# FRDM-Robot-Rev1_8.net
KiCad netlist of a schematic drawn in EAGLE
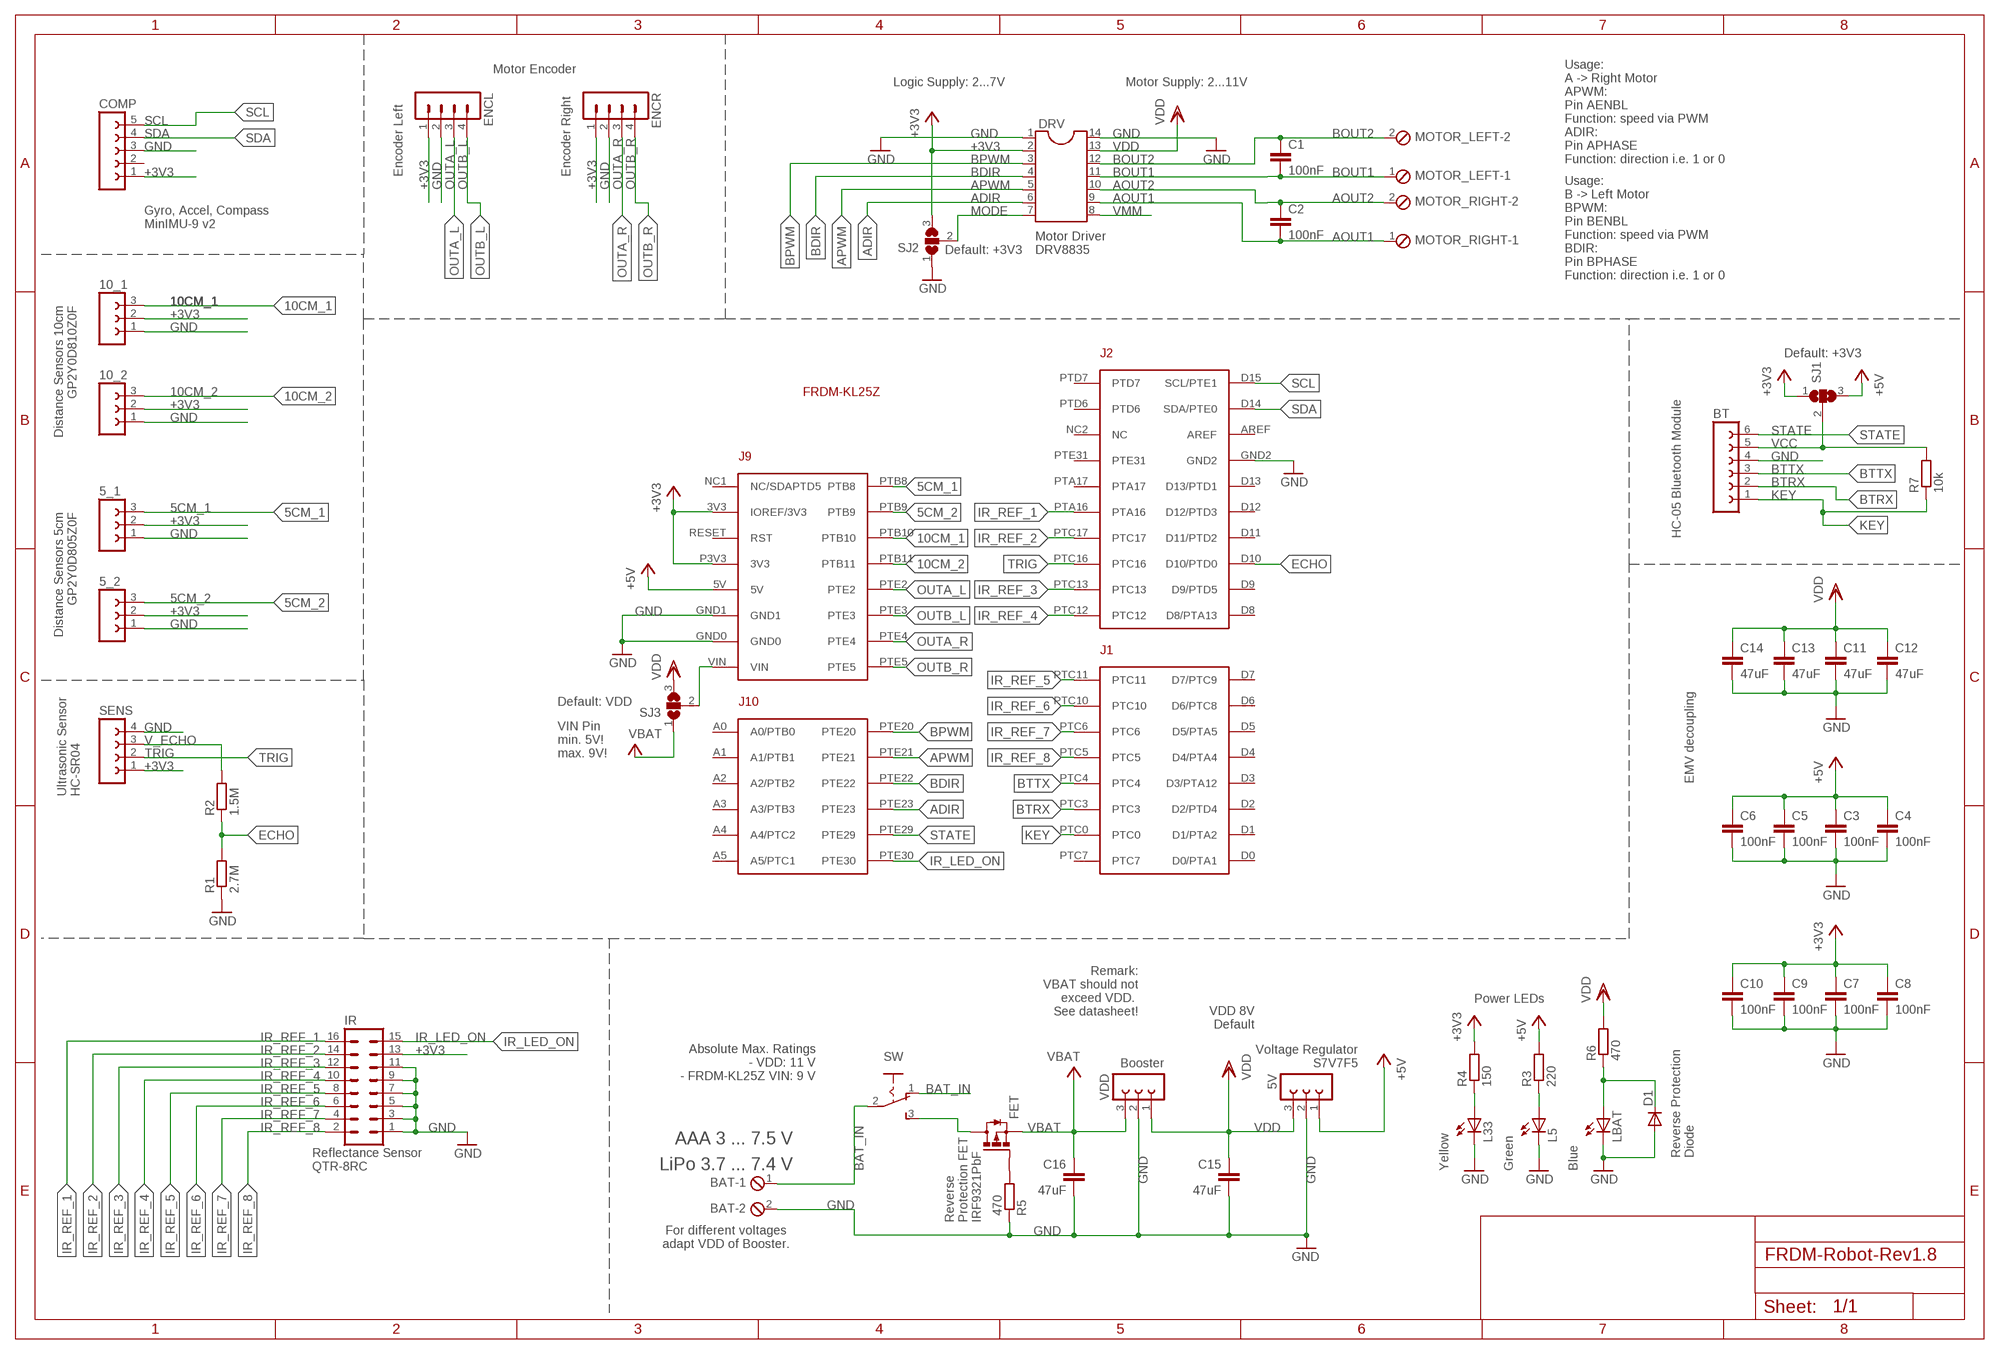
[diagram p0: schematic, sheet 1]

(export (version "E")
  (design (tool "Eeschema 10.0.6"))
  (components
    (comp (ref "5V")
      (value "FE03-1")
      (footprint "eagle-import:FE03-1")
      (libsource (lib "eagle-import") (part "FE03-1"))
    )
    (comp (ref "5_1")
      (value "FE03-1")
      (footprint "eagle-import:FE03-1")
      (libsource (lib "eagle-import") (part "FE03-1"))
    )
    (comp (ref "5_2")
      (value "FE03-1")
      (footprint "eagle-import:FE03-1")
      (libsource (lib "eagle-import") (part "FE03-1"))
    )
    (comp (ref "10_1")
      (value "FE03-1")
      (footprint "eagle-import:FE03-1")
      (libsource (lib "eagle-import") (part "FE03-1"))
    )
    (comp (ref "10_2")
      (value "FE03-1")
      (footprint "eagle-import:FE03-1")
      (libsource (lib "eagle-import") (part "FE03-1"))
    )
    (comp (ref "BAT")
      (value "MPT2")
      (footprint "eagle-import:2POL254")
      (libsource (lib "eagle-import") (part "MPT2"))
    )
    (comp (ref "BT")
      (value "FE06-1")
      (footprint "eagle-import:FE06")
      (libsource (lib "eagle-import") (part "FE06-1"))
    )
    (comp (ref "C1")
      (value "100nF")
      (footprint "eagle-import:C0805")
      (libsource (lib "eagle-import") (part "C-EUC0805"))
    )
    (comp (ref "C2")
      (value "100nF")
      (footprint "eagle-import:C0805")
      (libsource (lib "eagle-import") (part "C-EUC0805"))
    )
    (comp (ref "C3")
      (value "100nF")
      (footprint "eagle-import:C0805")
      (libsource (lib "eagle-import") (part "C-EUC0805"))
    )
    (comp (ref "C4")
      (value "100nF")
      (footprint "eagle-import:C0805")
      (libsource (lib "eagle-import") (part "C-EUC0805"))
    )
    (comp (ref "C5")
      (value "100nF")
      (footprint "eagle-import:C0805")
      (libsource (lib "eagle-import") (part "C-EUC0805"))
    )
    (comp (ref "C6")
      (value "100nF")
      (footprint "eagle-import:C0805")
      (libsource (lib "eagle-import") (part "C-EUC0805"))
    )
    (comp (ref "C7")
      (value "100nF")
      (footprint "eagle-import:C0805")
      (libsource (lib "eagle-import") (part "C-EUC0805"))
    )
    (comp (ref "C8")
      (value "100nF")
      (footprint "eagle-import:C0805")
      (libsource (lib "eagle-import") (part "C-EUC0805"))
    )
    (comp (ref "C9")
      (value "100nF")
      (footprint "eagle-import:C0805")
      (libsource (lib "eagle-import") (part "C-EUC0805"))
    )
    (comp (ref "C10")
      (value "100nF")
      (footprint "eagle-import:C0805")
      (libsource (lib "eagle-import") (part "C-EUC0805"))
    )
    (comp (ref "C11")
      (value "47uF")
      (footprint "eagle-import:C0805")
      (libsource (lib "eagle-import") (part "C-EUC0805"))
    )
    (comp (ref "C12")
      (value "47uF")
      (footprint "eagle-import:C0805")
      (libsource (lib "eagle-import") (part "C-EUC0805"))
    )
    (comp (ref "C13")
      (value "47uF")
      (footprint "eagle-import:C0805")
      (libsource (lib "eagle-import") (part "C-EUC0805"))
    )
    (comp (ref "C14")
      (value "47uF")
      (footprint "eagle-import:C0805")
      (libsource (lib "eagle-import") (part "C-EUC0805"))
    )
    (comp (ref "C15")
      (value "47uF")
      (footprint "eagle-import:C0805")
      (libsource (lib "eagle-import") (part "C-EUC0805"))
    )
    (comp (ref "C16")
      (value "47uF")
      (footprint "eagle-import:C0805")
      (libsource (lib "eagle-import") (part "C-EUC0805"))
    )
    (comp (ref "COMP")
      (value "FE05-1")
      (footprint "eagle-import:FE05-1")
      (libsource (lib "eagle-import") (part "FE05-1"))
    )
    (comp (ref "D1")
      (value "DIODE-SOD123")
      (footprint "eagle-import:SOD123")
      (libsource (lib "eagle-import") (part "DIODE-SOD123"))
    )
    (comp (ref "DRV")
      (value "DIL14")
      (footprint "eagle-import:DIL14")
      (libsource (lib "eagle-import") (part "DIL14"))
    )
    (comp (ref "ENCL")
      (value "MA04-1")
      (footprint "eagle-import:MA04-1")
      (libsource (lib "eagle-import") (part "MA04-1"))
    )
    (comp (ref "ENCR")
      (value "MA04-1")
      (footprint "eagle-import:MA04-1")
      (libsource (lib "eagle-import") (part "MA04-1"))
    )
    (comp (ref "FET")
      (value "P-MOSFET-SO8")
      (footprint "eagle-import:SO-08")
      (libsource (lib "eagle-import") (part "P-MOSFET-SO8"))
    )
    (comp (ref "FRDM1")
      (value "FRDM-KL25ZARDUINO")
      (footprint "eagle-import:FRDM-KL25Z")
      (libsource (lib "eagle-import") (part "FRDM-KL25ZARDUINO"))
    )
    (comp (ref "IR")
      (value "MA08-2")
      (footprint "eagle-import:MA08-2")
      (libsource (lib "eagle-import") (part "MA08-2"))
    )
    (comp (ref "L5")
      (value "LEDCHIP-LED0603")
      (footprint "eagle-import:CHIP-LED0603")
      (libsource (lib "eagle-import") (part "LEDCHIP-LED0603"))
    )
    (comp (ref "L33")
      (value "LEDCHIP-LED0603")
      (footprint "eagle-import:CHIP-LED0603")
      (libsource (lib "eagle-import") (part "LEDCHIP-LED0603"))
    )
    (comp (ref "LBAT")
      (value "LEDCHIP-LED0603")
      (footprint "eagle-import:CHIP-LED0603")
      (libsource (lib "eagle-import") (part "LEDCHIP-LED0603"))
    )
    (comp (ref "MOTOR_LEFT")
      (value "MPT2")
      (footprint "eagle-import:2POL254")
      (libsource (lib "eagle-import") (part "MPT2"))
    )
    (comp (ref "MOTOR_RIGHT")
      (value "MPT2")
      (footprint "eagle-import:2POL254")
      (libsource (lib "eagle-import") (part "MPT2"))
    )
    (comp (ref "R1")
      (value "2.7M")
      (footprint "eagle-import:M0805")
      (libsource (lib "eagle-import") (part "R-EU_M0805"))
    )
    (comp (ref "R2")
      (value "1.5M")
      (footprint "eagle-import:M0805")
      (libsource (lib "eagle-import") (part "R-EU_M0805"))
    )
    (comp (ref "R3")
      (value "220")
      (footprint "eagle-import:M0805")
      (libsource (lib "eagle-import") (part "R-EU_M0805"))
    )
    (comp (ref "R4")
      (value "150")
      (footprint "eagle-import:M0805")
      (libsource (lib "eagle-import") (part "R-EU_M0805"))
    )
    (comp (ref "R5")
      (value "470")
      (footprint "eagle-import:M0805")
      (libsource (lib "eagle-import") (part "R-EU_M0805"))
    )
    (comp (ref "R6")
      (value "470")
      (footprint "eagle-import:M0805")
      (libsource (lib "eagle-import") (part "R-EU_M0805"))
    )
    (comp (ref "R7")
      (value "10k")
      (footprint "eagle-import:M0805")
      (libsource (lib "eagle-import") (part "R-EU_M0805"))
    )
    (comp (ref "SENS")
      (value "FE04-1")
      (footprint "eagle-import:FE04-1")
      (libsource (lib "eagle-import") (part "FE04-1"))
    )
    (comp (ref "SJ1")
      (value "SJ2W")
      (footprint "eagle-import:SJ_2")
      (libsource (lib "eagle-import") (part "SJ2W"))
    )
    (comp (ref "SJ2")
      (value "SJ2W")
      (footprint "eagle-import:SJ_2")
      (libsource (lib "eagle-import") (part "SJ2W"))
    )
    (comp (ref "SJ3")
      (value "SJ2W")
      (footprint "eagle-import:SJ_2")
      (libsource (lib "eagle-import") (part "SJ2W"))
    )
    (comp (ref "SW")
      (value "KNITTER-MFP106D")
      (footprint "eagle-import:KNITTER-MFP106D")
      (libsource (lib "eagle-import") (part "KNITTER-MFP106D"))
    )
    (comp (ref "VDD")
      (value "FE03-1")
      (footprint "eagle-import:FE03-1")
      (libsource (lib "eagle-import") (part "FE03-1"))
    )
  )
  (nets
    (net (code "1") (name "+3V3") (class "Default")
      (node (ref "10_1") (pin "2") (pinfunction "2_2") (pintype "passive"))
      (node (ref "10_2") (pin "2") (pinfunction "2_2") (pintype "passive"))
      (node (ref "5_1") (pin "2") (pinfunction "2_2") (pintype "passive"))
      (node (ref "5_2") (pin "2") (pinfunction "2_2") (pintype "passive"))
      (node (ref "C10") (pin "1") (pinfunction "1_1") (pintype "passive"))
      (node (ref "C7") (pin "1") (pinfunction "1_1") (pintype "passive"))
      (node (ref "C8") (pin "1") (pinfunction "1_1") (pintype "passive"))
      (node (ref "C9") (pin "1") (pinfunction "1_1") (pintype "passive"))
      (node (ref "COMP") (pin "1") (pinfunction "1_1") (pintype "passive"))
      (node (ref "DRV") (pin "2") (pinfunction "2_2") (pintype "passive"))
      (node (ref "ENCL") (pin "1") (pinfunction "1_1") (pintype "passive"))
      (node (ref "ENCR") (pin "1") (pinfunction "1_1") (pintype "passive"))
      (node (ref "FRDM1") (pin "3V3") (pinfunction "IOREF/3V3_3V3") (pintype "bidirectional"))
      (node (ref "FRDM1") (pin "P3V3") (pinfunction "3V3_P3V3") (pintype "bidirectional"))
      (node (ref "IR") (pin "13") (pinfunction "13_13") (pintype "passive"))
      (node (ref "R4") (pin "2") (pinfunction "2_2") (pintype "passive"))
      (node (ref "SENS") (pin "1") (pinfunction "1_1") (pintype "passive"))
      (node (ref "SJ1") (pin "1") (pinfunction "1_1") (pintype "passive"))
      (node (ref "SJ2") (pin "3") (pinfunction "3_3") (pintype "passive"))
    )
    (net (code "2") (name "+5V") (class "Default")
      (node (ref "5V") (pin "1") (pinfunction "1_1") (pintype "passive"))
      (node (ref "C3") (pin "1") (pinfunction "1_1") (pintype "passive"))
      (node (ref "C4") (pin "1") (pinfunction "1_1") (pintype "passive"))
      (node (ref "C5") (pin "1") (pinfunction "1_1") (pintype "passive"))
      (node (ref "C6") (pin "1") (pinfunction "1_1") (pintype "passive"))
      (node (ref "FRDM1") (pin "5V") (pinfunction "5V_5V") (pintype "bidirectional"))
      (node (ref "R3") (pin "2") (pinfunction "2_2") (pintype "passive"))
      (node (ref "SJ1") (pin "3") (pinfunction "3_3") (pintype "passive"))
    )
    (net (code "3") (name "/AOUT1") (class "Default")
      (node (ref "C2") (pin "2") (pinfunction "2_2") (pintype "passive"))
      (node (ref "DRV") (pin "9") (pinfunction "9_9") (pintype "passive"))
      (node (ref "MOTOR_RIGHT") (pin "1") (pinfunction "1_1") (pintype "passive"))
    )
    (net (code "4") (name "/AOUT2") (class "Default")
      (node (ref "C2") (pin "1") (pinfunction "1_1") (pintype "passive"))
      (node (ref "DRV") (pin "10") (pinfunction "10_10") (pintype "passive"))
      (node (ref "MOTOR_RIGHT") (pin "2") (pinfunction "1_2") (pintype "passive"))
    )
    (net (code "5") (name "/BAT_IN") (class "Default")
      (node (ref "BAT") (pin "1") (pinfunction "1_1") (pintype "passive"))
      (node (ref "SW") (pin "1") (pinfunction "O_1") (pintype "passive"))
      (node (ref "SW") (pin "2") (pinfunction "P_2") (pintype "passive"))
    )
    (net (code "6") (name "/BOUT1") (class "Default")
      (node (ref "C1") (pin "2") (pinfunction "2_2") (pintype "passive"))
      (node (ref "DRV") (pin "11") (pinfunction "11_11") (pintype "passive"))
      (node (ref "MOTOR_LEFT") (pin "1") (pinfunction "1_1") (pintype "passive"))
    )
    (net (code "7") (name "/BOUT2") (class "Default")
      (node (ref "C1") (pin "1") (pinfunction "1_1") (pintype "passive"))
      (node (ref "DRV") (pin "12") (pinfunction "12_12") (pintype "passive"))
      (node (ref "MOTOR_LEFT") (pin "2") (pinfunction "1_2") (pintype "passive"))
    )
    (net (code "8") (name "/MODE") (class "Default")
      (node (ref "DRV") (pin "7") (pinfunction "7_7") (pintype "passive"))
      (node (ref "SJ2") (pin "2") (pinfunction "2_2") (pintype "passive"))
    )
    (net (code "9") (name "/VCC") (class "Default")
      (node (ref "BT") (pin "5") (pinfunction "5_5") (pintype "passive"))
      (node (ref "R7") (pin "2") (pinfunction "2_2") (pintype "passive"))
      (node (ref "SJ1") (pin "2") (pinfunction "2_2") (pintype "passive"))
    )
    (net (code "10") (name "/VMM") (class "Default")
      (node (ref "DRV") (pin "8") (pinfunction "8_8") (pintype "passive"))
    )
    (net (code "11") (name "/V_ECHO") (class "Default")
      (node (ref "R2") (pin "2") (pinfunction "2_2") (pintype "passive"))
      (node (ref "SENS") (pin "3") (pinfunction "3_3") (pintype "passive"))
    )
    (net (code "12") (name "5CM_1") (class "Default")
      (node (ref "5_1") (pin "3") (pinfunction "3_3") (pintype "passive"))
      (node (ref "FRDM1") (pin "PTB8") (pinfunction "PTB8_PTB8") (pintype "bidirectional"))
    )
    (net (code "13") (name "5CM_2") (class "Default")
      (node (ref "5_2") (pin "3") (pinfunction "3_3") (pintype "passive"))
      (node (ref "FRDM1") (pin "PTB9") (pinfunction "PTB9_PTB9") (pintype "bidirectional"))
    )
    (net (code "14") (name "10CM_1") (class "Default")
      (node (ref "10_1") (pin "3") (pinfunction "3_3") (pintype "passive"))
      (node (ref "FRDM1") (pin "PTB10") (pinfunction "PTB10_PTB10") (pintype "bidirectional"))
    )
    (net (code "15") (name "10CM_2") (class "Default")
      (node (ref "10_2") (pin "3") (pinfunction "3_3") (pintype "passive"))
      (node (ref "FRDM1") (pin "PTB11") (pinfunction "PTB11_PTB11") (pintype "bidirectional"))
    )
    (net (code "16") (name "ADIR") (class "Default")
      (node (ref "DRV") (pin "6") (pinfunction "6_6") (pintype "passive"))
      (node (ref "FRDM1") (pin "PTE23") (pinfunction "PTE23_PTE23") (pintype "bidirectional"))
    )
    (net (code "17") (name "APWM") (class "Default")
      (node (ref "DRV") (pin "5") (pinfunction "5_5") (pintype "passive"))
      (node (ref "FRDM1") (pin "PTE21") (pinfunction "PTE21_PTE21") (pintype "bidirectional"))
    )
    (net (code "18") (name "BDIR") (class "Default")
      (node (ref "DRV") (pin "4") (pinfunction "4_4") (pintype "passive"))
      (node (ref "FRDM1") (pin "PTE22") (pinfunction "PTE22_PTE22") (pintype "bidirectional"))
    )
    (net (code "19") (name "BPWM") (class "Default")
      (node (ref "DRV") (pin "3") (pinfunction "3_3") (pintype "passive"))
      (node (ref "FRDM1") (pin "PTE20") (pinfunction "PTE20_PTE20") (pintype "bidirectional"))
    )
    (net (code "20") (name "BTRX") (class "Default")
      (node (ref "BT") (pin "2") (pinfunction "2_2") (pintype "passive"))
      (node (ref "FRDM1") (pin "PTC3") (pinfunction "PTC3_PTC3") (pintype "bidirectional"))
    )
    (net (code "21") (name "BTTX") (class "Default")
      (node (ref "BT") (pin "3") (pinfunction "3_3") (pintype "passive"))
      (node (ref "FRDM1") (pin "PTC4") (pinfunction "PTC4_PTC4") (pintype "bidirectional"))
    )
    (net (code "22") (name "ECHO") (class "Default")
      (node (ref "FRDM1") (pin "D10") (pinfunction "D10/PTD0_D10") (pintype "bidirectional"))
      (node (ref "R1") (pin "2") (pinfunction "2_2") (pintype "passive"))
      (node (ref "R2") (pin "1") (pinfunction "1_1") (pintype "passive"))
    )
    (net (code "23") (name "GND") (class "Default")
      (node (ref "10_1") (pin "1") (pinfunction "1_1") (pintype "passive"))
      (node (ref "10_2") (pin "1") (pinfunction "1_1") (pintype "passive"))
      (node (ref "5V") (pin "2") (pinfunction "2_2") (pintype "passive"))
      (node (ref "5_1") (pin "1") (pinfunction "1_1") (pintype "passive"))
      (node (ref "5_2") (pin "1") (pinfunction "1_1") (pintype "passive"))
      (node (ref "BAT") (pin "2") (pinfunction "1_2") (pintype "passive"))
      (node (ref "BT") (pin "4") (pinfunction "4_4") (pintype "passive"))
      (node (ref "C10") (pin "2") (pinfunction "2_2") (pintype "passive"))
      (node (ref "C11") (pin "2") (pinfunction "2_2") (pintype "passive"))
      (node (ref "C12") (pin "2") (pinfunction "2_2") (pintype "passive"))
      (node (ref "C13") (pin "2") (pinfunction "2_2") (pintype "passive"))
      (node (ref "C14") (pin "2") (pinfunction "2_2") (pintype "passive"))
      (node (ref "C15") (pin "2") (pinfunction "2_2") (pintype "passive"))
      (node (ref "C16") (pin "2") (pinfunction "2_2") (pintype "passive"))
      (node (ref "C3") (pin "2") (pinfunction "2_2") (pintype "passive"))
      (node (ref "C4") (pin "2") (pinfunction "2_2") (pintype "passive"))
      (node (ref "C5") (pin "2") (pinfunction "2_2") (pintype "passive"))
      (node (ref "C6") (pin "2") (pinfunction "2_2") (pintype "passive"))
      (node (ref "C7") (pin "2") (pinfunction "2_2") (pintype "passive"))
      (node (ref "C8") (pin "2") (pinfunction "2_2") (pintype "passive"))
      (node (ref "C9") (pin "2") (pinfunction "2_2") (pintype "passive"))
      (node (ref "COMP") (pin "3") (pinfunction "3_3") (pintype "passive"))
      (node (ref "D1") (pin "A") (pinfunction "A_A") (pintype "passive"))
      (node (ref "DRV") (pin "1") (pinfunction "1_1") (pintype "passive"))
      (node (ref "DRV") (pin "14") (pinfunction "14_14") (pintype "passive"))
      (node (ref "ENCL") (pin "2") (pinfunction "2_2") (pintype "passive"))
      (node (ref "ENCR") (pin "2") (pinfunction "2_2") (pintype "passive"))
      (node (ref "FRDM1") (pin "GND0") (pinfunction "GND0_GND0") (pintype "bidirectional"))
      (node (ref "FRDM1") (pin "GND1") (pinfunction "GND1_GND1") (pintype "bidirectional"))
      (node (ref "FRDM1") (pin "GND2") (pinfunction "GND2_GND2") (pintype "bidirectional"))
      (node (ref "IR") (pin "1") (pinfunction "1_1") (pintype "passive"))
      (node (ref "IR") (pin "11") (pinfunction "11_11") (pintype "passive"))
      (node (ref "IR") (pin "3") (pinfunction "3_3") (pintype "passive"))
      (node (ref "IR") (pin "5") (pinfunction "5_5") (pintype "passive"))
      (node (ref "IR") (pin "7") (pinfunction "7_7") (pintype "passive"))
      (node (ref "IR") (pin "9") (pinfunction "9_9") (pintype "passive"))
      (node (ref "L33") (pin "C") (pinfunction "C_C") (pintype "passive"))
      (node (ref "L5") (pin "C") (pinfunction "C_C") (pintype "passive"))
      (node (ref "LBAT") (pin "C") (pinfunction "C_C") (pintype "passive"))
      (node (ref "R1") (pin "1") (pinfunction "1_1") (pintype "passive"))
      (node (ref "R5") (pin "1") (pinfunction "1_1") (pintype "passive"))
      (node (ref "SENS") (pin "4") (pinfunction "4_4") (pintype "passive"))
      (node (ref "SJ2") (pin "1") (pinfunction "1_1") (pintype "passive"))
      (node (ref "VDD") (pin "2") (pinfunction "2_2") (pintype "passive"))
    )
    (net (code "24") (name "IR_LED_ON") (class "Default")
      (node (ref "FRDM1") (pin "PTE30") (pinfunction "PTE30_PTE30") (pintype "bidirectional"))
      (node (ref "IR") (pin "15") (pinfunction "15_15") (pintype "passive"))
    )
    (net (code "25") (name "IR_REF_1") (class "Default")
      (node (ref "FRDM1") (pin "PTA16") (pinfunction "PTA16_PTA16") (pintype "bidirectional"))
      (node (ref "IR") (pin "16") (pinfunction "16_16") (pintype "passive"))
    )
    (net (code "26") (name "IR_REF_2") (class "Default")
      (node (ref "FRDM1") (pin "PTC17") (pinfunction "PTC17_PTC17") (pintype "bidirectional"))
      (node (ref "IR") (pin "14") (pinfunction "14_14") (pintype "passive"))
    )
    (net (code "27") (name "IR_REF_3") (class "Default")
      (node (ref "FRDM1") (pin "PTC13") (pinfunction "PTC13_PTC13") (pintype "bidirectional"))
      (node (ref "IR") (pin "12") (pinfunction "12_12") (pintype "passive"))
    )
    (net (code "28") (name "IR_REF_4") (class "Default")
      (node (ref "FRDM1") (pin "PTC12") (pinfunction "PTC12_PTC12") (pintype "bidirectional"))
      (node (ref "IR") (pin "10") (pinfunction "10_10") (pintype "passive"))
    )
    (net (code "29") (name "IR_REF_5") (class "Default")
      (node (ref "FRDM1") (pin "PTC11") (pinfunction "PTC11_PTC11") (pintype "bidirectional"))
      (node (ref "IR") (pin "8") (pinfunction "8_8") (pintype "passive"))
    )
    (net (code "30") (name "IR_REF_6") (class "Default")
      (node (ref "FRDM1") (pin "PTC10") (pinfunction "PTC10_PTC10") (pintype "bidirectional"))
      (node (ref "IR") (pin "6") (pinfunction "6_6") (pintype "passive"))
    )
    (net (code "31") (name "IR_REF_7") (class "Default")
      (node (ref "FRDM1") (pin "PTC6") (pinfunction "PTC6_PTC6") (pintype "bidirectional"))
      (node (ref "IR") (pin "4") (pinfunction "4_4") (pintype "passive"))
    )
    (net (code "32") (name "IR_REF_8") (class "Default")
      (node (ref "FRDM1") (pin "PTC5") (pinfunction "PTC5_PTC5") (pintype "bidirectional"))
      (node (ref "IR") (pin "2") (pinfunction "2_2") (pintype "passive"))
    )
    (net (code "33") (name "KEY") (class "Default")
      (node (ref "BT") (pin "1") (pinfunction "1_1") (pintype "passive"))
      (node (ref "FRDM1") (pin "PTC0") (pinfunction "PTC0_PTC0") (pintype "bidirectional"))
      (node (ref "R7") (pin "1") (pinfunction "1_1") (pintype "passive"))
    )
    (net (code "34") (name "Net-(D1-PadC)") (class "Default")
      (node (ref "D1") (pin "C") (pinfunction "C_C") (pintype "passive"))
      (node (ref "LBAT") (pin "A") (pinfunction "A_A") (pintype "passive"))
      (node (ref "R6") (pin "1") (pinfunction "1_1") (pintype "passive"))
    )
    (net (code "35") (name "Net-(FET-G)") (class "Default")
      (node (ref "FET") (pin "4") (pinfunction "G_4") (pintype "passive"))
      (node (ref "R5") (pin "2") (pinfunction "2_2") (pintype "passive"))
    )
    (net (code "36") (name "Net-(FRDM1-PadVIN)") (class "Default")
      (node (ref "FRDM1") (pin "VIN") (pinfunction "VIN_VIN") (pintype "bidirectional"))
      (node (ref "SJ3") (pin "2") (pinfunction "2_2") (pintype "passive"))
    )
    (net (code "37") (name "Net-(L5-PadA)") (class "Default")
      (node (ref "L5") (pin "A") (pinfunction "A_A") (pintype "passive"))
      (node (ref "R3") (pin "1") (pinfunction "1_1") (pintype "passive"))
    )
    (net (code "38") (name "Net-(L33-PadA)") (class "Default")
      (node (ref "L33") (pin "A") (pinfunction "A_A") (pintype "passive"))
      (node (ref "R4") (pin "1") (pinfunction "1_1") (pintype "passive"))
    )
    (net (code "39") (name "Net-(SW-S)") (class "Default")
      (node (ref "FET") (pin "5") (pinfunction "D_5") (pintype "passive"))
      (node (ref "FET") (pin "6") (pinfunction "D_6") (pintype "passive"))
      (node (ref "FET") (pin "7") (pinfunction "D_7") (pintype "passive"))
      (node (ref "FET") (pin "8") (pinfunction "D_8") (pintype "passive"))
      (node (ref "SW") (pin "3") (pinfunction "S_3") (pintype "passive"))
    )
    (net (code "40") (name "OUTA_L") (class "Default")
      (node (ref "ENCL") (pin "3") (pinfunction "3_3") (pintype "passive"))
      (node (ref "FRDM1") (pin "PTE2") (pinfunction "PTE2_PTE2") (pintype "bidirectional"))
    )
    (net (code "41") (name "OUTA_R") (class "Default")
      (node (ref "ENCR") (pin "3") (pinfunction "3_3") (pintype "passive"))
      (node (ref "FRDM1") (pin "PTE4") (pinfunction "PTE4_PTE4") (pintype "bidirectional"))
    )
    (net (code "42") (name "OUTB_L") (class "Default")
      (node (ref "ENCL") (pin "4") (pinfunction "4_4") (pintype "passive"))
      (node (ref "FRDM1") (pin "PTE3") (pinfunction "PTE3_PTE3") (pintype "bidirectional"))
    )
    (net (code "43") (name "OUTB_R") (class "Default")
      (node (ref "ENCR") (pin "4") (pinfunction "4_4") (pintype "passive"))
      (node (ref "FRDM1") (pin "PTE5") (pinfunction "PTE5_PTE5") (pintype "bidirectional"))
    )
    (net (code "44") (name "SCL") (class "Default")
      (node (ref "COMP") (pin "5") (pinfunction "5_5") (pintype "passive"))
      (node (ref "FRDM1") (pin "D15") (pinfunction "SCL/PTE1_D15") (pintype "bidirectional"))
    )
    (net (code "45") (name "SDA") (class "Default")
      (node (ref "COMP") (pin "4") (pinfunction "4_4") (pintype "passive"))
      (node (ref "FRDM1") (pin "D14") (pinfunction "SDA/PTE0_D14") (pintype "bidirectional"))
    )
    (net (code "46") (name "STATE") (class "Default")
      (node (ref "BT") (pin "6") (pinfunction "6_6") (pintype "passive"))
      (node (ref "FRDM1") (pin "PTE29") (pinfunction "PTE29_PTE29") (pintype "bidirectional"))
    )
    (net (code "47") (name "TRIG") (class "Default")
      (node (ref "FRDM1") (pin "PTC16") (pinfunction "PTC16_PTC16") (pintype "bidirectional"))
      (node (ref "SENS") (pin "2") (pinfunction "2_2") (pintype "passive"))
    )
    (net (code "48") (name "VBAT") (class "Default")
      (node (ref "C16") (pin "1") (pinfunction "1_1") (pintype "passive"))
      (node (ref "FET") (pin "1") (pinfunction "S_1") (pintype "passive"))
      (node (ref "FET") (pin "2") (pinfunction "S_2") (pintype "passive"))
      (node (ref "FET") (pin "3") (pinfunction "S_3") (pintype "passive"))
      (node (ref "SJ3") (pin "1") (pinfunction "1_1") (pintype "passive"))
      (node (ref "VDD") (pin "3") (pinfunction "3_3") (pintype "passive"))
    )
    (net (code "49") (name "VDD") (class "Default")
      (node (ref "5V") (pin "3") (pinfunction "3_3") (pintype "passive"))
      (node (ref "C11") (pin "1") (pinfunction "1_1") (pintype "passive"))
      (node (ref "C12") (pin "1") (pinfunction "1_1") (pintype "passive"))
      (node (ref "C13") (pin "1") (pinfunction "1_1") (pintype "passive"))
      (node (ref "C14") (pin "1") (pinfunction "1_1") (pintype "passive"))
      (node (ref "C15") (pin "1") (pinfunction "1_1") (pintype "passive"))
      (node (ref "DRV") (pin "13") (pinfunction "13_13") (pintype "passive"))
      (node (ref "R6") (pin "2") (pinfunction "2_2") (pintype "passive"))
      (node (ref "SJ3") (pin "3") (pinfunction "3_3") (pintype "passive"))
      (node (ref "VDD") (pin "1") (pinfunction "1_1") (pintype "passive"))
    )
    (net (code "50") (name "unconnected-(COMP-Pad2)") (class "Default")
      (node (ref "COMP") (pin "2") (pinfunction "2_2") (pintype "passive"))
    )
    (net (code "51") (name "unconnected-(FRDM1-A0{slash}PTB0-PadA0)") (class "Default")
      (node (ref "FRDM1") (pin "A0") (pinfunction "A0/PTB0_A0") (pintype "bidirectional"))
    )
    (net (code "52") (name "unconnected-(FRDM1-A1{slash}PTB1-PadA1)") (class "Default")
      (node (ref "FRDM1") (pin "A1") (pinfunction "A1/PTB1_A1") (pintype "bidirectional"))
    )
    (net (code "53") (name "unconnected-(FRDM1-A2{slash}PTB2-PadA2)") (class "Default")
      (node (ref "FRDM1") (pin "A2") (pinfunction "A2/PTB2_A2") (pintype "bidirectional"))
    )
    (net (code "54") (name "unconnected-(FRDM1-A3{slash}PTB3-PadA3)") (class "Default")
      (node (ref "FRDM1") (pin "A3") (pinfunction "A3/PTB3_A3") (pintype "bidirectional"))
    )
    (net (code "55") (name "unconnected-(FRDM1-A4{slash}PTC2-PadA4)") (class "Default")
      (node (ref "FRDM1") (pin "A4") (pinfunction "A4/PTC2_A4") (pintype "bidirectional"))
    )
    (net (code "56") (name "unconnected-(FRDM1-A5{slash}PTC1-PadA5)") (class "Default")
      (node (ref "FRDM1") (pin "A5") (pinfunction "A5/PTC1_A5") (pintype "bidirectional"))
    )
    (net (code "57") (name "unconnected-(FRDM1-D0{slash}PTA1-PadD0)") (class "Default")
      (node (ref "FRDM1") (pin "D0") (pinfunction "D0/PTA1_D0") (pintype "bidirectional"))
    )
    (net (code "58") (name "unconnected-(FRDM1-D1{slash}PTA2-PadD1)") (class "Default")
      (node (ref "FRDM1") (pin "D1") (pinfunction "D1/PTA2_D1") (pintype "bidirectional"))
    )
    (net (code "59") (name "unconnected-(FRDM1-D2{slash}PTD4-PadD2)") (class "Default")
      (node (ref "FRDM1") (pin "D2") (pinfunction "D2/PTD4_D2") (pintype "bidirectional"))
    )
    (net (code "60") (name "unconnected-(FRDM1-D3{slash}PTA12-PadD3)") (class "Default")
      (node (ref "FRDM1") (pin "D3") (pinfunction "D3/PTA12_D3") (pintype "bidirectional"))
    )
    (net (code "61") (name "unconnected-(FRDM1-D4{slash}PTA4-PadD4)") (class "Default")
      (node (ref "FRDM1") (pin "D4") (pinfunction "D4/PTA4_D4") (pintype "bidirectional"))
    )
    (net (code "62") (name "unconnected-(FRDM1-D5{slash}PTA5-PadD5)") (class "Default")
      (node (ref "FRDM1") (pin "D5") (pinfunction "D5/PTA5_D5") (pintype "bidirectional"))
    )
    (net (code "63") (name "unconnected-(FRDM1-D6{slash}PTC8-PadD6)") (class "Default")
      (node (ref "FRDM1") (pin "D6") (pinfunction "D6/PTC8_D6") (pintype "bidirectional"))
    )
    (net (code "64") (name "unconnected-(FRDM1-D7{slash}PTC9-PadD7)") (class "Default")
      (node (ref "FRDM1") (pin "D7") (pinfunction "D7/PTC9_D7") (pintype "bidirectional"))
    )
    (net (code "65") (name "unconnected-(FRDM1-D8{slash}PTA13-PadD8)") (class "Default")
      (node (ref "FRDM1") (pin "D8") (pinfunction "D8/PTA13_D8") (pintype "bidirectional"))
    )
    (net (code "66") (name "unconnected-(FRDM1-D9{slash}PTD5-PadD9)") (class "Default")
      (node (ref "FRDM1") (pin "D9") (pinfunction "D9/PTD5_D9") (pintype "bidirectional"))
    )
    (net (code "67") (name "unconnected-(FRDM1-D11{slash}PTD2-PadD11)") (class "Default")
      (node (ref "FRDM1") (pin "D11") (pinfunction "D11/PTD2_D11") (pintype "bidirectional"))
    )
    (net (code "68") (name "unconnected-(FRDM1-D12{slash}PTD3-PadD12)") (class "Default")
      (node (ref "FRDM1") (pin "D12") (pinfunction "D12/PTD3_D12") (pintype "bidirectional"))
    )
    (net (code "69") (name "unconnected-(FRDM1-D13{slash}PTD1-PadD13)") (class "Default")
      (node (ref "FRDM1") (pin "D13") (pinfunction "D13/PTD1_D13") (pintype "bidirectional"))
    )
    (net (code "70") (name "unconnected-(FRDM1-NC-PadNC2)") (class "Default")
      (node (ref "FRDM1") (pin "NC2") (pinfunction "NC_NC2") (pintype "bidirectional"))
    )
    (net (code "71") (name "unconnected-(FRDM1-NC{slash}SDAPTD5-PadNC1)") (class "Default")
      (node (ref "FRDM1") (pin "NC1") (pinfunction "NC/SDAPTD5_NC1") (pintype "bidirectional"))
    )
    (net (code "72") (name "unconnected-(FRDM1-PadAREF)") (class "Default")
      (node (ref "FRDM1") (pin "AREF") (pinfunction "AREF_AREF") (pintype "bidirectional"))
    )
    (net (code "73") (name "unconnected-(FRDM1-PadPTA17)") (class "Default")
      (node (ref "FRDM1") (pin "PTA17") (pinfunction "PTA17_PTA17") (pintype "bidirectional"))
    )
    (net (code "74") (name "unconnected-(FRDM1-PadPTC7)") (class "Default")
      (node (ref "FRDM1") (pin "PTC7") (pinfunction "PTC7_PTC7") (pintype "bidirectional"))
    )
    (net (code "75") (name "unconnected-(FRDM1-PadPTD6)") (class "Default")
      (node (ref "FRDM1") (pin "PTD6") (pinfunction "PTD6_PTD6") (pintype "bidirectional"))
    )
    (net (code "76") (name "unconnected-(FRDM1-PadPTD7)") (class "Default")
      (node (ref "FRDM1") (pin "PTD7") (pinfunction "PTD7_PTD7") (pintype "bidirectional"))
    )
    (net (code "77") (name "unconnected-(FRDM1-PadPTE31)") (class "Default")
      (node (ref "FRDM1") (pin "PTE31") (pinfunction "PTE31_PTE31") (pintype "bidirectional"))
    )
    (net (code "78") (name "unconnected-(FRDM1-RST-PadRESET)") (class "Default")
      (node (ref "FRDM1") (pin "RESET") (pinfunction "RST_RESET") (pintype "bidirectional"))
    )
  )
)
